# carte_A.net
KiCad netlist of a schematic drawn in EAGLE
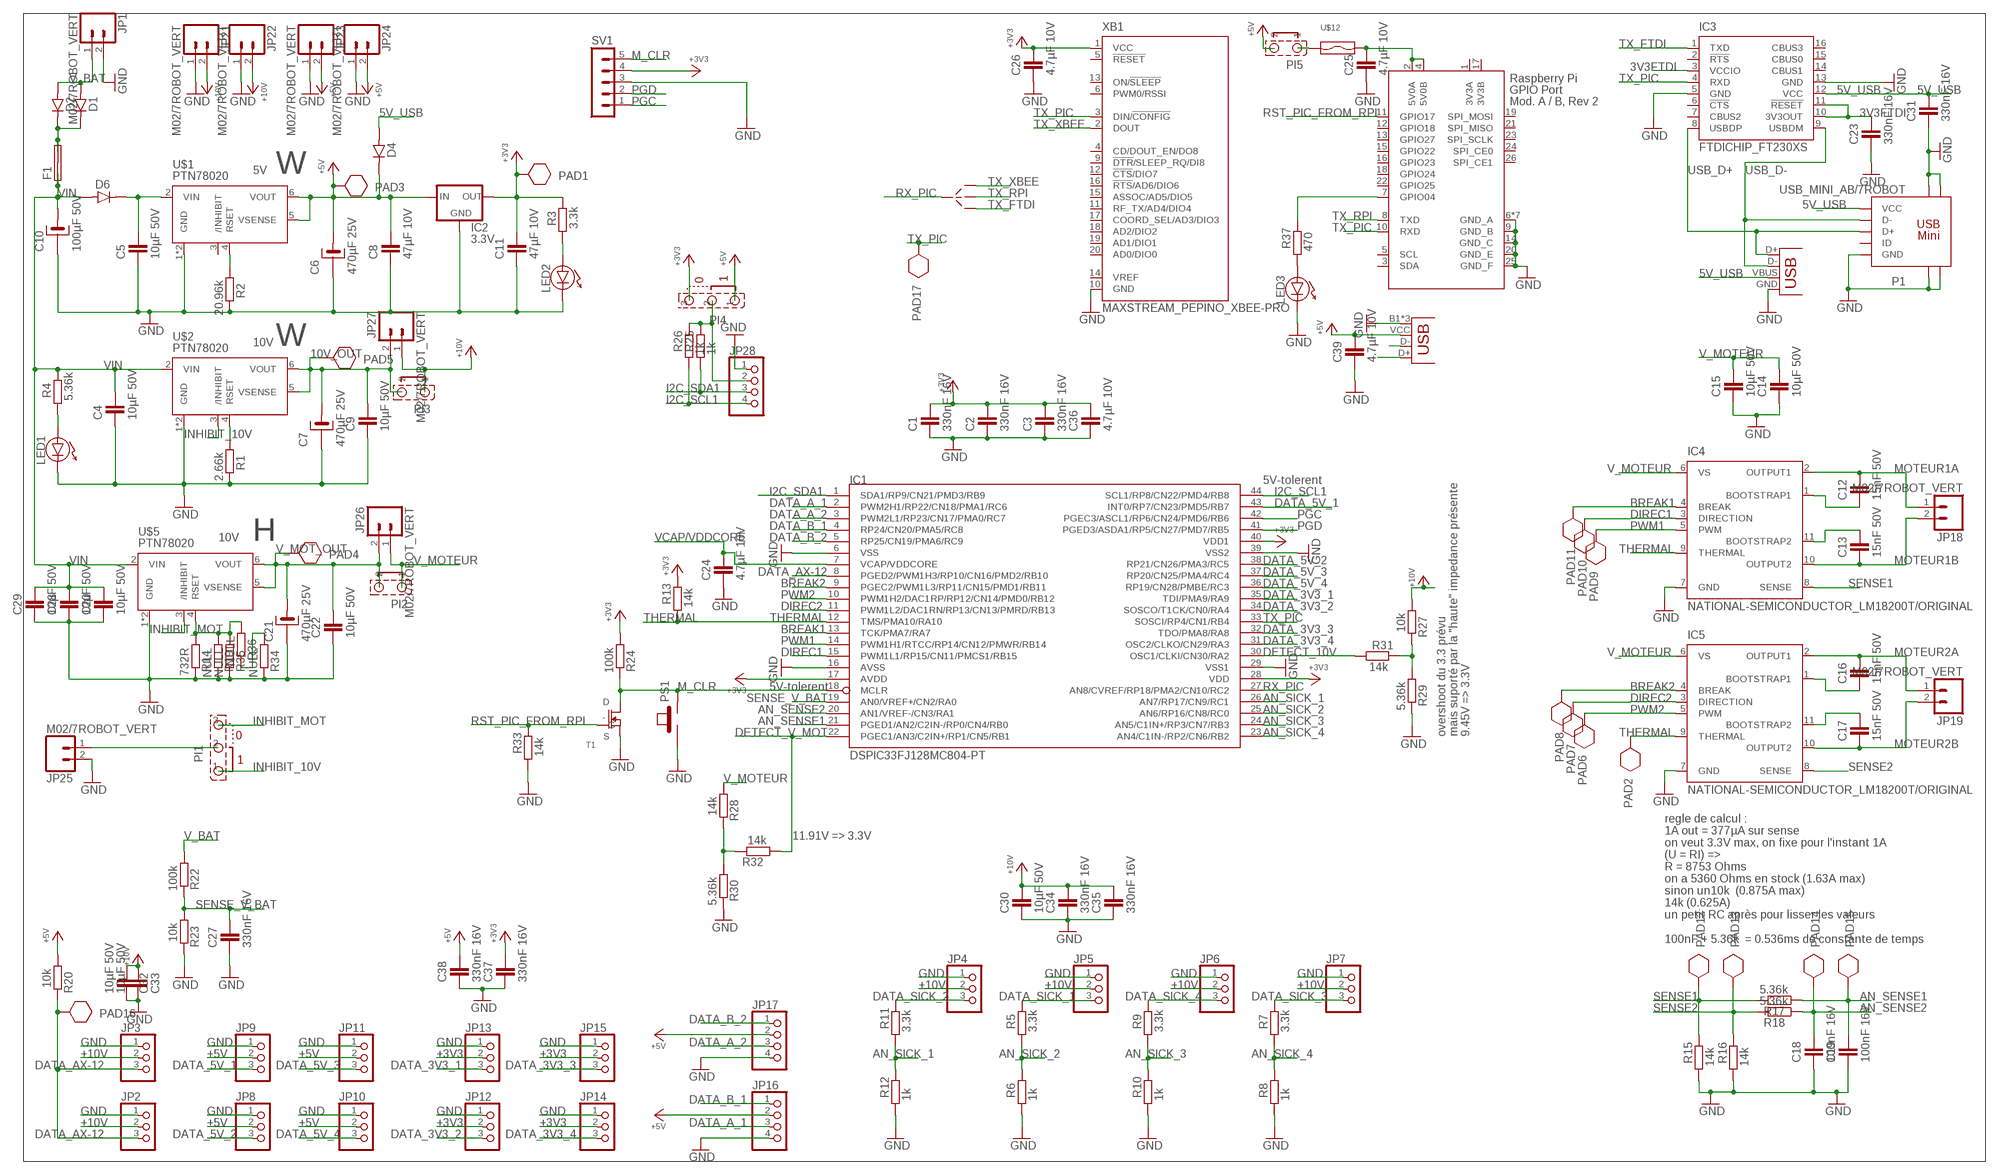
[diagram p0: schematic, sheet 1]

(export (version "E")
  (design (tool "Eeschema 10.0.6"))
  (components
    (comp (ref "C1")
      (value "330nF 16V")
      (footprint "eagle-import:0805")
      (libsource (lib "eagle-import") (part "C_CERAMIQUE/0805"))
    )
    (comp (ref "C2")
      (value "330nF 16V")
      (footprint "eagle-import:0805")
      (libsource (lib "eagle-import") (part "C_CERAMIQUE/0805"))
    )
    (comp (ref "C3")
      (value "330nF 16V")
      (footprint "eagle-import:0805")
      (libsource (lib "eagle-import") (part "C_CERAMIQUE/0805"))
    )
    (comp (ref "C4")
      (value "10µF 50V")
      (footprint "eagle-import:1206")
      (libsource (lib "eagle-import") (part "C_CERAMIQUE/1206"))
    )
    (comp (ref "C5")
      (value "10µF 50V")
      (footprint "eagle-import:1206")
      (libsource (lib "eagle-import") (part "C_CERAMIQUE/1206"))
    )
    (comp (ref "C6")
      (value "470µF 25V")
      (footprint "eagle-import:CHIM8P3.5")
      (libsource (lib "eagle-import") (part "C_CHIMIQUE/RADIAL_8X10_PAS3.5"))
    )
    (comp (ref "C7")
      (value "470µF 25V")
      (footprint "eagle-import:CHIM8P3.5")
      (libsource (lib "eagle-import") (part "C_CHIMIQUE/RADIAL_8X10_PAS3.5"))
    )
    (comp (ref "C8")
      (value "47µF 10V")
      (footprint "eagle-import:1210")
      (libsource (lib "eagle-import") (part "C_CERAMIQUE/1210"))
    )
    (comp (ref "C9")
      (value "10µF 50V")
      (footprint "eagle-import:1206")
      (libsource (lib "eagle-import") (part "C_CERAMIQUE/1206"))
    )
    (comp (ref "C10")
      (value "100µF 50V")
      (footprint "eagle-import:CHIM8P3.5")
      (libsource (lib "eagle-import") (part "C_CHIMIQUE/RADIAL_8X10_PAS3.5"))
    )
    (comp (ref "C11")
      (value "47µF 10V")
      (footprint "eagle-import:1210")
      (libsource (lib "eagle-import") (part "C_CERAMIQUE/1210"))
    )
    (comp (ref "C12")
      (value "15nF 50V")
      (footprint "eagle-import:0805")
      (libsource (lib "eagle-import") (part "C_CERAMIQUE/0805"))
    )
    (comp (ref "C13")
      (value "15nF 50V")
      (footprint "eagle-import:0805")
      (libsource (lib "eagle-import") (part "C_CERAMIQUE/0805"))
    )
    (comp (ref "C14")
      (value "10µF 50V")
      (footprint "eagle-import:1206")
      (libsource (lib "eagle-import") (part "C_CERAMIQUE/1206"))
    )
    (comp (ref "C15")
      (value "10µF 50V")
      (footprint "eagle-import:1206")
      (libsource (lib "eagle-import") (part "C_CERAMIQUE/1206"))
    )
    (comp (ref "C16")
      (value "15nF 50V")
      (footprint "eagle-import:0805")
      (libsource (lib "eagle-import") (part "C_CERAMIQUE/0805"))
    )
    (comp (ref "C17")
      (value "15nF 50V")
      (footprint "eagle-import:0805")
      (libsource (lib "eagle-import") (part "C_CERAMIQUE/0805"))
    )
    (comp (ref "C18")
      (value "100nF 16V")
      (footprint "eagle-import:0805")
      (libsource (lib "eagle-import") (part "C_CERAMIQUE/0805"))
    )
    (comp (ref "C19")
      (value "100nF 16V")
      (footprint "eagle-import:0805")
      (libsource (lib "eagle-import") (part "C_CERAMIQUE/0805"))
    )
    (comp (ref "C20")
      (value "10µF 50V")
      (footprint "eagle-import:1206")
      (libsource (lib "eagle-import") (part "C_CERAMIQUE/1206"))
    )
    (comp (ref "C21")
      (value "470µF 25V")
      (footprint "eagle-import:CHIM8P3.5")
      (libsource (lib "eagle-import") (part "C_CHIMIQUE/RADIAL_8X10_PAS3.5"))
    )
    (comp (ref "C22")
      (value "10µF 50V")
      (footprint "eagle-import:1206")
      (libsource (lib "eagle-import") (part "C_CERAMIQUE/1206"))
    )
    (comp (ref "C23")
      (value "330nF 16V")
      (footprint "eagle-import:0805")
      (libsource (lib "eagle-import") (part "C_CERAMIQUE/0805"))
    )
    (comp (ref "C24")
      (value "4.7µF 10V")
      (footprint "eagle-import:0805")
      (libsource (lib "eagle-import") (part "C_CERAMIQUE/0805"))
    )
    (comp (ref "C25")
      (value "4.7µF 10V")
      (footprint "eagle-import:0805")
      (libsource (lib "eagle-import") (part "C_CERAMIQUE/0805"))
    )
    (comp (ref "C26")
      (value "4.7µF 10V")
      (footprint "eagle-import:0805")
      (libsource (lib "eagle-import") (part "C_CERAMIQUE/0805"))
    )
    (comp (ref "C27")
      (value "330nF 16V")
      (footprint "eagle-import:0805")
      (libsource (lib "eagle-import") (part "C_CERAMIQUE/0805"))
    )
    (comp (ref "C28")
      (value "10µF 50V")
      (footprint "eagle-import:1206")
      (libsource (lib "eagle-import") (part "C_CERAMIQUE/1206"))
    )
    (comp (ref "C29")
      (value "10µF 50V")
      (footprint "eagle-import:1206")
      (libsource (lib "eagle-import") (part "C_CERAMIQUE/1206"))
    )
    (comp (ref "C30")
      (value "10µF 50V")
      (footprint "eagle-import:1206")
      (libsource (lib "eagle-import") (part "C_CERAMIQUE/1206"))
    )
    (comp (ref "C31")
      (value "330nF 16V")
      (footprint "eagle-import:0805")
      (libsource (lib "eagle-import") (part "C_CERAMIQUE/0805"))
    )
    (comp (ref "C32")
      (value "10µF 50V")
      (footprint "eagle-import:1206")
      (libsource (lib "eagle-import") (part "C_CERAMIQUE/1206"))
    )
    (comp (ref "C33")
      (value "10µF 50V")
      (footprint "eagle-import:1206")
      (libsource (lib "eagle-import") (part "C_CERAMIQUE/1206"))
    )
    (comp (ref "C34")
      (value "330nF 16V")
      (footprint "eagle-import:0805")
      (libsource (lib "eagle-import") (part "C_CERAMIQUE/0805"))
    )
    (comp (ref "C35")
      (value "330nF 16V")
      (footprint "eagle-import:0805")
      (libsource (lib "eagle-import") (part "C_CERAMIQUE/0805"))
    )
    (comp (ref "C36")
      (value "4.7µF 10V")
      (footprint "eagle-import:0805")
      (libsource (lib "eagle-import") (part "C_CERAMIQUE/0805"))
    )
    (comp (ref "C37")
      (value "330nF 16V")
      (footprint "eagle-import:0805")
      (libsource (lib "eagle-import") (part "C_CERAMIQUE/0805"))
    )
    (comp (ref "C38")
      (value "330nF 16V")
      (footprint "eagle-import:0805")
      (libsource (lib "eagle-import") (part "C_CERAMIQUE/0805"))
    )
    (comp (ref "C39")
      (value "4.7µF 10V")
      (footprint "eagle-import:0805")
      (libsource (lib "eagle-import") (part "C_CERAMIQUE/0805"))
    )
    (comp (ref "D1")
      (value "DIODES_DIODE/DO41")
      (footprint "eagle-import:DIODES_DO41")
      (libsource (lib "eagle-import") (part "DIODES_DIODE/DO41"))
    )
    (comp (ref "D2")
      (value "DIODES_DIODE/DO41")
      (footprint "eagle-import:DIODES_DO41")
      (libsource (lib "eagle-import") (part "DIODES_DIODE/DO41"))
    )
    (comp (ref "D4")
      (value "DIODES_DIODE/DO41")
      (footprint "eagle-import:DIODES_DO41")
      (libsource (lib "eagle-import") (part "DIODES_DIODE/DO41"))
    )
    (comp (ref "D6")
      (value "DIODES_DIODE/DO41")
      (footprint "eagle-import:DIODES_DO41")
      (libsource (lib "eagle-import") (part "DIODES_DIODE/DO41"))
    )
    (comp (ref "F1")
      (value "PORTE_FUSIBLE")
      (footprint "eagle-import:SHK20L")
      (libsource (lib "eagle-import") (part "PORTE_FUSIBLE"))
    )
    (comp (ref "IC1")
      (value "DSPIC33FJ128MC804-PT")
      (footprint "eagle-import:TQFP44")
      (libsource (lib "eagle-import") (part "DSPIC33FJ128MC804-PT"))
    )
    (comp (ref "IC2")
      (value "3.3V")
      (footprint "eagle-import:V-REG_78XXS")
      (libsource (lib "eagle-import") (part "V-REG_78XXS"))
    )
    (comp (ref "IC3")
      (value "FTDICHIP_FT230XS")
      (footprint "eagle-import:FTDICHIP_SSOP16")
      (libsource (lib "eagle-import") (part "FTDICHIP_FT230XS"))
    )
    (comp (ref "IC4")
      (value "NATIONAL-SEMICONDUCTOR_LM18200T/ORIGINAL")
      (footprint "eagle-import:NATIONAL-SEMICONDUCTOR_TO-220-11")
      (libsource (lib "eagle-import") (part "NATIONAL-SEMICONDUCTOR_LM18200T/ORIGINAL"))
    )
    (comp (ref "IC5")
      (value "NATIONAL-SEMICONDUCTOR_LM18200T/ORIGINAL")
      (footprint "eagle-import:NATIONAL-SEMICONDUCTOR_TO-220-11")
      (libsource (lib "eagle-import") (part "NATIONAL-SEMICONDUCTOR_LM18200T/ORIGINAL"))
    )
    (comp (ref "JP1")
      (value "M02/7ROBOT_VERT")
      (footprint "eagle-import:CONN_5MM")
      (libsource (lib "eagle-import") (part "M02/7ROBOT_VERT"))
    )
    (comp (ref "JP2")
      (value "PINHD-1X3")
      (footprint "eagle-import:1X03")
      (libsource (lib "eagle-import") (part "PINHD-1X3"))
    )
    (comp (ref "JP3")
      (value "PINHD-1X3")
      (footprint "eagle-import:1X03")
      (libsource (lib "eagle-import") (part "PINHD-1X3"))
    )
    (comp (ref "JP4")
      (value "PINHD-1X3")
      (footprint "eagle-import:1X03")
      (libsource (lib "eagle-import") (part "PINHD-1X3"))
    )
    (comp (ref "JP5")
      (value "PINHD-1X3")
      (footprint "eagle-import:1X03")
      (libsource (lib "eagle-import") (part "PINHD-1X3"))
    )
    (comp (ref "JP6")
      (value "PINHD-1X3")
      (footprint "eagle-import:1X03")
      (libsource (lib "eagle-import") (part "PINHD-1X3"))
    )
    (comp (ref "JP7")
      (value "PINHD-1X3")
      (footprint "eagle-import:1X03")
      (libsource (lib "eagle-import") (part "PINHD-1X3"))
    )
    (comp (ref "JP8")
      (value "PINHD-1X3")
      (footprint "eagle-import:1X03")
      (libsource (lib "eagle-import") (part "PINHD-1X3"))
    )
    (comp (ref "JP9")
      (value "PINHD-1X3")
      (footprint "eagle-import:1X03")
      (libsource (lib "eagle-import") (part "PINHD-1X3"))
    )
    (comp (ref "JP10")
      (value "PINHD-1X3")
      (footprint "eagle-import:1X03")
      (libsource (lib "eagle-import") (part "PINHD-1X3"))
    )
    (comp (ref "JP11")
      (value "PINHD-1X3")
      (footprint "eagle-import:1X03")
      (libsource (lib "eagle-import") (part "PINHD-1X3"))
    )
    (comp (ref "JP12")
      (value "PINHD-1X3")
      (footprint "eagle-import:1X03")
      (libsource (lib "eagle-import") (part "PINHD-1X3"))
    )
    (comp (ref "JP13")
      (value "PINHD-1X3")
      (footprint "eagle-import:1X03")
      (libsource (lib "eagle-import") (part "PINHD-1X3"))
    )
    (comp (ref "JP14")
      (value "PINHD-1X3")
      (footprint "eagle-import:1X03")
      (libsource (lib "eagle-import") (part "PINHD-1X3"))
    )
    (comp (ref "JP15")
      (value "PINHD-1X3")
      (footprint "eagle-import:1X03")
      (libsource (lib "eagle-import") (part "PINHD-1X3"))
    )
    (comp (ref "JP16")
      (value "PINHD-1X4")
      (footprint "eagle-import:1X04")
      (libsource (lib "eagle-import") (part "PINHD-1X4"))
    )
    (comp (ref "JP17")
      (value "PINHD-1X4")
      (footprint "eagle-import:1X04")
      (libsource (lib "eagle-import") (part "PINHD-1X4"))
    )
    (comp (ref "JP18")
      (value "M02/7ROBOT_VERT")
      (footprint "eagle-import:CONN_5MM")
      (libsource (lib "eagle-import") (part "M02/7ROBOT_VERT"))
    )
    (comp (ref "JP19")
      (value "M02/7ROBOT_VERT")
      (footprint "eagle-import:CONN_5MM")
      (libsource (lib "eagle-import") (part "M02/7ROBOT_VERT"))
    )
    (comp (ref "JP20")
      (value "USB-B")
      (footprint "eagle-import:SPARKFUN-CONNECTORS_USB-B-PTH")
      (libsource (lib "eagle-import") (part "SPARKFUN-CONNECTORS_USBPTH"))
    )
    (comp (ref "JP21")
      (value "M02/7ROBOT_VERT")
      (footprint "eagle-import:CONN_5MM")
      (libsource (lib "eagle-import") (part "M02/7ROBOT_VERT"))
    )
    (comp (ref "JP22")
      (value "M02/7ROBOT_VERT")
      (footprint "eagle-import:CONN_5MM")
      (libsource (lib "eagle-import") (part "M02/7ROBOT_VERT"))
    )
    (comp (ref "JP23")
      (value "M02/7ROBOT_VERT")
      (footprint "eagle-import:CONN_5MM")
      (libsource (lib "eagle-import") (part "M02/7ROBOT_VERT"))
    )
    (comp (ref "JP24")
      (value "M02/7ROBOT_VERT")
      (footprint "eagle-import:CONN_5MM")
      (libsource (lib "eagle-import") (part "M02/7ROBOT_VERT"))
    )
    (comp (ref "JP25")
      (value "M02/7ROBOT_VERT")
      (footprint "eagle-import:CONN_5MM")
      (libsource (lib "eagle-import") (part "M02/7ROBOT_VERT"))
    )
    (comp (ref "JP26")
      (value "M02/7ROBOT_VERT")
      (footprint "eagle-import:CONN_5MM")
      (libsource (lib "eagle-import") (part "M02/7ROBOT_VERT"))
    )
    (comp (ref "JP27")
      (value "M02/7ROBOT_VERT")
      (footprint "eagle-import:CONN_5MM")
      (libsource (lib "eagle-import") (part "M02/7ROBOT_VERT"))
    )
    (comp (ref "JP28")
      (value "PINHD-1X4")
      (footprint "eagle-import:1X04")
      (libsource (lib "eagle-import") (part "PINHD-1X4"))
    )
    (comp (ref "JP29")
      (value "USB/VERT")
      (footprint "eagle-import:USB-A-FEMALE_VERTICAL")
      (libsource (lib "eagle-import") (part "USB/VERT"))
    )
    (comp (ref "LED1")
      (value "OPTO_OSC_LED/5MM")
      (footprint "eagle-import:OPTO_OSC_LED5")
      (libsource (lib "eagle-import") (part "OPTO_OSC_LED/5MM"))
    )
    (comp (ref "LED2")
      (value "OPTO_OSC_LED/5MM")
      (footprint "eagle-import:OPTO_OSC_LED5")
      (libsource (lib "eagle-import") (part "OPTO_OSC_LED/5MM"))
    )
    (comp (ref "LED3")
      (value "LED/1206")
      (footprint "eagle-import:LED1206")
      (libsource (lib "eagle-import") (part "LED/1206"))
    )
    (comp (ref "P1")
      (value "USB_MINI_AB/7ROBOT")
      (footprint "eagle-import:USB_MINI_AB_7ROBOT")
      (libsource (lib "eagle-import") (part "USB_MINI_AB/7ROBOT"))
    )
    (comp (ref "PAD1")
      (value "STRAP_PAD/CMS2")
      (footprint "eagle-import:STRAP_PAD_CMS_2")
      (libsource (lib "eagle-import") (part "STRAP_PAD/CMS2"))
    )
    (comp (ref "PAD2")
      (value "STRAP_PAD/CMS1_5")
      (footprint "eagle-import:STRAP_PAD_CMS_1_5")
      (libsource (lib "eagle-import") (part "STRAP_PAD/CMS1_5"))
    )
    (comp (ref "PAD3")
      (value "STRAP_PAD/CMS2")
      (footprint "eagle-import:STRAP_PAD_CMS_2")
      (libsource (lib "eagle-import") (part "STRAP_PAD/CMS2"))
    )
    (comp (ref "PAD4")
      (value "STRAP_PAD/CMS2")
      (footprint "eagle-import:STRAP_PAD_CMS_2")
      (libsource (lib "eagle-import") (part "STRAP_PAD/CMS2"))
    )
    (comp (ref "PAD5")
      (value "STRAP_PAD/CMS2")
      (footprint "eagle-import:STRAP_PAD_CMS_2")
      (libsource (lib "eagle-import") (part "STRAP_PAD/CMS2"))
    )
    (comp (ref "PAD6")
      (value "STRAP_PAD/CMS1_5")
      (footprint "eagle-import:STRAP_PAD_CMS_1_5")
      (libsource (lib "eagle-import") (part "STRAP_PAD/CMS1_5"))
    )
    (comp (ref "PAD7")
      (value "STRAP_PAD/CMS1_5")
      (footprint "eagle-import:STRAP_PAD_CMS_1_5")
      (libsource (lib "eagle-import") (part "STRAP_PAD/CMS1_5"))
    )
    (comp (ref "PAD8")
      (value "STRAP_PAD/CMS1_5")
      (footprint "eagle-import:STRAP_PAD_CMS_1_5")
      (libsource (lib "eagle-import") (part "STRAP_PAD/CMS1_5"))
    )
    (comp (ref "PAD9")
      (value "STRAP_PAD/CMS1_5")
      (footprint "eagle-import:STRAP_PAD_CMS_1_5")
      (libsource (lib "eagle-import") (part "STRAP_PAD/CMS1_5"))
    )
    (comp (ref "PAD10")
      (value "STRAP_PAD/CMS1_5")
      (footprint "eagle-import:STRAP_PAD_CMS_1_5")
      (libsource (lib "eagle-import") (part "STRAP_PAD/CMS1_5"))
    )
    (comp (ref "PAD11")
      (value "STRAP_PAD/CMS1_5")
      (footprint "eagle-import:STRAP_PAD_CMS_1_5")
      (libsource (lib "eagle-import") (part "STRAP_PAD/CMS1_5"))
    )
    (comp (ref "PAD12")
      (value "STRAP_PAD/CMS1_5")
      (footprint "eagle-import:STRAP_PAD_CMS_1_5")
      (libsource (lib "eagle-import") (part "STRAP_PAD/CMS1_5"))
    )
    (comp (ref "PAD13")
      (value "STRAP_PAD/CMS1_5")
      (footprint "eagle-import:STRAP_PAD_CMS_1_5")
      (libsource (lib "eagle-import") (part "STRAP_PAD/CMS1_5"))
    )
    (comp (ref "PAD14")
      (value "STRAP_PAD/CMS1_5")
      (footprint "eagle-import:STRAP_PAD_CMS_1_5")
      (libsource (lib "eagle-import") (part "STRAP_PAD/CMS1_5"))
    )
    (comp (ref "PAD15")
      (value "STRAP_PAD/CMS1_5")
      (footprint "eagle-import:STRAP_PAD_CMS_1_5")
      (libsource (lib "eagle-import") (part "STRAP_PAD/CMS1_5"))
    )
    (comp (ref "PAD16")
      (value "STRAP_PAD/CMS1_5")
      (footprint "eagle-import:STRAP_PAD_CMS_1_5")
      (libsource (lib "eagle-import") (part "STRAP_PAD/CMS1_5"))
    )
    (comp (ref "PAD17")
      (value "STRAP_PAD/CMS2")
      (footprint "eagle-import:STRAP_PAD_CMS_2")
      (libsource (lib "eagle-import") (part "STRAP_PAD/CMS2"))
    )
    (comp (ref "PI1")
      (value "STCMS_3/CMS")
      (footprint "eagle-import:STCMS_3")
      (libsource (lib "eagle-import") (part "STCMS_3/CMS"))
    )
    (comp (ref "PI2")
      (value "STCMS_2")
      (footprint "eagle-import:STCMS_2")
      (libsource (lib "eagle-import") (part "STCMS_2"))
    )
    (comp (ref "PI3")
      (value "STCMS_2")
      (footprint "eagle-import:STCMS_2")
      (libsource (lib "eagle-import") (part "STCMS_2"))
    )
    (comp (ref "PI4")
      (value "STCMS_3/CMS")
      (footprint "eagle-import:STCMS_3")
      (libsource (lib "eagle-import") (part "STCMS_3/CMS"))
    )
    (comp (ref "PI5")
      (value "STCMS_2")
      (footprint "eagle-import:STCMS_2")
      (libsource (lib "eagle-import") (part "STCMS_2"))
    )
    (comp (ref "PS1")
      (value "ELECTROMECA_PEPINO_POUSSOIR/D_MINI")
      (footprint "eagle-import:ELECTROMECA_PEPINO_B3F")
      (libsource (lib "eagle-import") (part "ELECTROMECA_PEPINO_POUSSOIR/D_MINI"))
    )
    (comp (ref "R1")
      (value "2.66k")
      (footprint "eagle-import:0805")
      (libsource (lib "eagle-import") (part "RES/0805"))
    )
    (comp (ref "R2")
      (value "20.96k")
      (footprint "eagle-import:0805")
      (libsource (lib "eagle-import") (part "RES/0805"))
    )
    (comp (ref "R3")
      (value "3.3k")
      (footprint "eagle-import:0805")
      (libsource (lib "eagle-import") (part "RES/0805"))
    )
    (comp (ref "R4")
      (value "5.36k")
      (footprint "eagle-import:0805")
      (libsource (lib "eagle-import") (part "RES/0805"))
    )
    (comp (ref "R5")
      (value "3.3k")
      (footprint "eagle-import:0805")
      (libsource (lib "eagle-import") (part "RES/0805"))
    )
    (comp (ref "R6")
      (value "1k")
      (footprint "eagle-import:0805")
      (libsource (lib "eagle-import") (part "RES/0805"))
    )
    (comp (ref "R7")
      (value "3.3k")
      (footprint "eagle-import:0805")
      (libsource (lib "eagle-import") (part "RES/0805"))
    )
    (comp (ref "R8")
      (value "1k")
      (footprint "eagle-import:0805")
      (libsource (lib "eagle-import") (part "RES/0805"))
    )
    (comp (ref "R9")
      (value "3.3k")
      (footprint "eagle-import:0805")
      (libsource (lib "eagle-import") (part "RES/0805"))
    )
    (comp (ref "R10")
      (value "1k")
      (footprint "eagle-import:0805")
      (libsource (lib "eagle-import") (part "RES/0805"))
    )
    (comp (ref "R11")
      (value "3.3k")
      (footprint "eagle-import:0805")
      (libsource (lib "eagle-import") (part "RES/0805"))
    )
    (comp (ref "R12")
      (value "1k")
      (footprint "eagle-import:0805")
      (libsource (lib "eagle-import") (part "RES/0805"))
    )
    (comp (ref "R13")
      (value "14k")
      (footprint "eagle-import:0805")
      (libsource (lib "eagle-import") (part "RES/0805"))
    )
    (comp (ref "R14")
      (value "732R")
      (footprint "eagle-import:0805")
      (libsource (lib "eagle-import") (part "RES/0805"))
    )
    (comp (ref "R15")
      (value "14k")
      (footprint "eagle-import:0805")
      (libsource (lib "eagle-import") (part "RES/0805"))
    )
    (comp (ref "R16")
      (value "14k")
      (footprint "eagle-import:0805")
      (libsource (lib "eagle-import") (part "RES/0805"))
    )
    (comp (ref "R17")
      (value "5.36k")
      (footprint "eagle-import:0805")
      (libsource (lib "eagle-import") (part "RES/0805"))
    )
    (comp (ref "R18")
      (value "5.36k")
      (footprint "eagle-import:0805")
      (libsource (lib "eagle-import") (part "RES/0805"))
    )
    (comp (ref "R19")
      (value "NULL")
      (footprint "eagle-import:0805")
      (libsource (lib "eagle-import") (part "RES/0805"))
    )
    (comp (ref "R20")
      (value "10k")
      (footprint "eagle-import:1206")
      (libsource (lib "eagle-import") (part "RES/1206"))
    )
    (comp (ref "R22")
      (value "100k")
      (footprint "eagle-import:1206")
      (libsource (lib "eagle-import") (part "RES/1206"))
    )
    (comp (ref "R23")
      (value "10k")
      (footprint "eagle-import:1206")
      (libsource (lib "eagle-import") (part "RES/1206"))
    )
    (comp (ref "R24")
      (value "100k")
      (footprint "eagle-import:1206")
      (libsource (lib "eagle-import") (part "RES/1206"))
    )
    (comp (ref "R25")
      (value "1k")
      (footprint "eagle-import:0805")
      (libsource (lib "eagle-import") (part "RES/0805"))
    )
    (comp (ref "R26")
      (value "1k")
      (footprint "eagle-import:0805")
      (libsource (lib "eagle-import") (part "RES/0805"))
    )
    (comp (ref "R27")
      (value "10k")
      (footprint "eagle-import:1206")
      (libsource (lib "eagle-import") (part "RES/1206"))
    )
    (comp (ref "R28")
      (value "14k")
      (footprint "eagle-import:0805")
      (libsource (lib "eagle-import") (part "RES/0805"))
    )
    (comp (ref "R29")
      (value "5.36k")
      (footprint "eagle-import:0805")
      (libsource (lib "eagle-import") (part "RES/0805"))
    )
    (comp (ref "R30")
      (value "5.36k")
      (footprint "eagle-import:0805")
      (libsource (lib "eagle-import") (part "RES/0805"))
    )
    (comp (ref "R31")
      (value "14k")
      (footprint "eagle-import:0805")
      (libsource (lib "eagle-import") (part "RES/0805"))
    )
    (comp (ref "R32")
      (value "14k")
      (footprint "eagle-import:0805")
      (libsource (lib "eagle-import") (part "RES/0805"))
    )
    (comp (ref "R33")
      (value "14k")
      (footprint "eagle-import:0805")
      (libsource (lib "eagle-import") (part "RES/0805"))
    )
    (comp (ref "R34")
      (value "NULL")
      (footprint "eagle-import:0805")
      (libsource (lib "eagle-import") (part "RES/0805"))
    )
    (comp (ref "R35")
      (value "NULL")
      (footprint "eagle-import:0805")
      (libsource (lib "eagle-import") (part "RES/0805"))
    )
    (comp (ref "R36")
      (value "NULL")
      (footprint "eagle-import:0805")
      (libsource (lib "eagle-import") (part "RES/0805"))
    )
    (comp (ref "R37")
      (value "470")
      (footprint "eagle-import:0805")
      (libsource (lib "eagle-import") (part "RES/0805"))
    )
    (comp (ref "SV1")
      (value "CON-LSTB_MA05-1")
      (footprint "eagle-import:CON-LSTB_MA05-1")
      (libsource (lib "eagle-import") (part "CON-LSTB_MA05-1"))
    )
    (comp (ref "T1")
      (value "MOS_N/SOT23")
      (footprint "eagle-import:SOT23")
      (libsource (lib "eagle-import") (part "MOS_N/SOT23"))
    )
    (comp (ref "U$1")
      (value "PTN78020")
      (footprint "eagle-import:PTN78020")
      (libsource (lib "eagle-import") (part "PTN78020"))
    )
    (comp (ref "U$2")
      (value "PTN78020")
      (footprint "eagle-import:PTN78020")
      (libsource (lib "eagle-import") (part "PTN78020"))
    )
    (comp (ref "U$5")
      (value "PTN78020")
      (footprint "eagle-import:PTN78020")
      (libsource (lib "eagle-import") (part "PTN78020"))
    )
    (comp (ref "U$9")
      (value "STCMS_4")
      (footprint "eagle-import:STCMS_4")
      (libsource (lib "eagle-import") (part "STCMS_4"))
    )
    (comp (ref "U$12")
      (value "FUSE_REARMABLE/1206")
      (footprint "eagle-import:1206")
      (libsource (lib "eagle-import") (part "FUSE_REARMABLE/1206"))
    )
    (comp (ref "X1")
      (value "RASPI_BOARD_B-#_E6P")
      (footprint "eagle-import:RASPI_BOARD_AB-_EDGES_6DRILL_PAD")
      (libsource (lib "eagle-import") (part "RASPI_BOARD_B-#_E6P"))
    )
    (comp (ref "XB1")
      (value "MAXSTREAM_PEPINO_XBEE-PRO")
      (footprint "eagle-import:MAXSTREAM_PEPINO_XBEE-PRO")
      (fields (field (name "MPN") "XBP24-AWI-001"))
      (libsource (lib "eagle-import") (part "MAXSTREAM_PEPINO_XBEE-PRO"))
    )
  )
  (nets
    (net (code "1") (name "+3V3") (class "Default")
      (node (ref "C1") (pin "1") (pinfunction "1_1") (pintype "passive"))
      (node (ref "C11") (pin "1") (pinfunction "1_1") (pintype "passive"))
      (node (ref "C2") (pin "1") (pinfunction "1_1") (pintype "passive"))
      (node (ref "C26") (pin "1") (pinfunction "1_1") (pintype "passive"))
      (node (ref "C3") (pin "1") (pinfunction "1_1") (pintype "passive"))
      (node (ref "C36") (pin "1") (pinfunction "1_1") (pintype "passive"))
      (node (ref "C37") (pin "1") (pinfunction "1_1") (pintype "passive"))
      (node (ref "IC1") (pin "17") (pinfunction "AVDD_17") (pintype "power_in"))
      (node (ref "IC1") (pin "28") (pinfunction "VDD_28") (pintype "power_in"))
      (node (ref "IC1") (pin "40") (pinfunction "VDD1_40") (pintype "power_in"))
      (node (ref "IC2") (pin "OUT") (pinfunction "OUT_OUT") (pintype "passive"))
      (node (ref "JP12") (pin "2") (pinfunction "2_2") (pintype "passive"))
      (node (ref "JP13") (pin "2") (pinfunction "2_2") (pintype "passive"))
      (node (ref "JP14") (pin "2") (pinfunction "2_2") (pintype "passive"))
      (node (ref "JP15") (pin "2") (pinfunction "2_2") (pintype "passive"))
      (node (ref "PAD1") (pin "P$1") (pinfunction "P$1_P$1") (pintype "bidirectional"))
      (node (ref "PI4") (pin "3") (pinfunction "3_3") (pintype "bidirectional"))
      (node (ref "R13") (pin "2") (pinfunction "2_2") (pintype "passive"))
      (node (ref "R24") (pin "1") (pinfunction "1_1") (pintype "passive"))
      (node (ref "R3") (pin "2") (pinfunction "2_2") (pintype "passive"))
      (node (ref "SV1") (pin "4") (pinfunction "4_4") (pintype "passive"))
      (node (ref "XB1") (pin "1") (pinfunction "VCC_1") (pintype "power_in"))
    )
    (net (code "2") (name "+5V") (class "Default")
      (node (ref "C38") (pin "1") (pinfunction "1_1") (pintype "passive"))
      (node (ref "C39") (pin "1") (pinfunction "1_1") (pintype "passive"))
      (node (ref "C6") (pin "P") (pinfunction "P_P") (pintype "passive"))
      (node (ref "C8") (pin "1") (pinfunction "1_1") (pintype "passive"))
      (node (ref "D4") (pin "K") (pinfunction "K_K") (pintype "passive"))
      (node (ref "IC2") (pin "IN") (pinfunction "IN_IN") (pintype "input"))
      (node (ref "JP10") (pin "2") (pinfunction "2_2") (pintype "passive"))
      (node (ref "JP11") (pin "2") (pinfunction "2_2") (pintype "passive"))
      (node (ref "JP16") (pin "2") (pinfunction "2_2") (pintype "passive"))
      (node (ref "JP17") (pin "2") (pinfunction "2_2") (pintype "passive"))
      (node (ref "JP23") (pin "2") (pinfunction "2_2") (pintype "passive"))
      (node (ref "JP24") (pin "2") (pinfunction "2_2") (pintype "passive"))
      (node (ref "JP29") (pin "VCC") (pinfunction "VBUS_VCC") (pintype "bidirectional"))
      (node (ref "JP8") (pin "2") (pinfunction "2_2") (pintype "passive"))
      (node (ref "JP9") (pin "2") (pinfunction "2_2") (pintype "passive"))
      (node (ref "PAD3") (pin "P$1") (pinfunction "P$1_P$1") (pintype "bidirectional"))
      (node (ref "PI4") (pin "1") (pinfunction "1_1") (pintype "bidirectional"))
      (node (ref "PI5") (pin "2") (pinfunction "2_2") (pintype "bidirectional"))
      (node (ref "R20") (pin "1") (pinfunction "1_1") (pintype "passive"))
      (node (ref "U$1") (pin "5") (pinfunction "VSENSE_5") (pintype "bidirectional"))
      (node (ref "U$1") (pin "6") (pinfunction "VOUT_6") (pintype "bidirectional"))
    )
    (net (code "3") (name "+10V") (class "Default")
      (node (ref "C30") (pin "1") (pinfunction "1_1") (pintype "passive"))
      (node (ref "C32") (pin "1") (pinfunction "1_1") (pintype "passive"))
      (node (ref "C33") (pin "1") (pinfunction "1_1") (pintype "passive"))
      (node (ref "C34") (pin "1") (pinfunction "1_1") (pintype "passive"))
      (node (ref "C35") (pin "1") (pinfunction "1_1") (pintype "passive"))
      (node (ref "JP2") (pin "2") (pinfunction "2_2") (pintype "passive"))
      (node (ref "JP21") (pin "2") (pinfunction "2_2") (pintype "passive"))
      (node (ref "JP22") (pin "2") (pinfunction "2_2") (pintype "passive"))
      (node (ref "JP27") (pin "1") (pinfunction "1_1") (pintype "passive"))
      (node (ref "JP3") (pin "2") (pinfunction "2_2") (pintype "passive"))
      (node (ref "JP4") (pin "2") (pinfunction "2_2") (pintype "passive"))
      (node (ref "JP5") (pin "2") (pinfunction "2_2") (pintype "passive"))
      (node (ref "JP6") (pin "2") (pinfunction "2_2") (pintype "passive"))
      (node (ref "JP7") (pin "2") (pinfunction "2_2") (pintype "passive"))
      (node (ref "PI3") (pin "1") (pinfunction "1_1") (pintype "bidirectional"))
      (node (ref "R27") (pin "1") (pinfunction "1_1") (pintype "passive"))
    )
    (net (code "4") (name "/3V3A") (class "Default")
      (node (ref "X1") (pin "1") (pinfunction "3V3A_1") (pintype "power_in"))
    )
    (net (code "5") (name "/3V3B") (class "Default")
      (node (ref "X1") (pin "17") (pinfunction "3V3B_17") (pintype "power_in"))
    )
    (net (code "6") (name "/3V3FTDI") (class "Default")
      (node (ref "C23") (pin "1") (pinfunction "1_1") (pintype "passive"))
      (node (ref "IC3") (pin "10") (pinfunction "3V3OUT_10") (pintype "output"))
      (node (ref "IC3") (pin "11") (pinfunction "~{RESET}_11") (pintype "input"))
      (node (ref "IC3") (pin "3") (pinfunction "VCCIO_3") (pintype "power_in"))
    )
    (net (code "7") (name "/5V_USB") (class "Default")
      (node (ref "C31") (pin "1") (pinfunction "1_1") (pintype "passive"))
      (node (ref "D4") (pin "A") (pinfunction "A_A") (pintype "passive"))
      (node (ref "IC3") (pin "12") (pinfunction "VCC_12") (pintype "power_in"))
      (node (ref "JP20") (pin "VBUS") (pinfunction "VBUS_VBUS") (pintype "bidirectional"))
      (node (ref "P1") (pin "1") (pinfunction "VCC_1") (pintype "bidirectional"))
    )
    (net (code "8") (name "/10V_OUT") (class "Default")
      (node (ref "C7") (pin "P") (pinfunction "P_P") (pintype "passive"))
      (node (ref "C9") (pin "1") (pinfunction "1_1") (pintype "passive"))
      (node (ref "JP27") (pin "2") (pinfunction "2_2") (pintype "passive"))
      (node (ref "PAD5") (pin "P$1") (pinfunction "P$1_P$1") (pintype "bidirectional"))
      (node (ref "PI3") (pin "2") (pinfunction "2_2") (pintype "bidirectional"))
      (node (ref "U$2") (pin "5") (pinfunction "VSENSE_5") (pintype "bidirectional"))
      (node (ref "U$2") (pin "6") (pinfunction "VOUT_6") (pintype "bidirectional"))
    )
    (net (code "9") (name "/AN_SENSE1") (class "Default")
      (node (ref "C19") (pin "1") (pinfunction "1_1") (pintype "passive"))
      (node (ref "IC1") (pin "21") (pinfunction "PGED1/AN2/C2IN-/RP0/CN4/RB0_21") (pintype "bidirectional"))
      (node (ref "PAD15") (pin "P$1") (pinfunction "P$1_P$1") (pintype "bidirectional"))
      (node (ref "R17") (pin "1") (pinfunction "1_1") (pintype "passive"))
    )
    (net (code "10") (name "/AN_SENSE2") (class "Default")
      (node (ref "C18") (pin "1") (pinfunction "1_1") (pintype "passive"))
      (node (ref "IC1") (pin "20") (pinfunction "AN1/VREF-/CN3/RA1_20") (pintype "bidirectional"))
      (node (ref "PAD14") (pin "P$1") (pinfunction "P$1_P$1") (pintype "bidirectional"))
      (node (ref "R18") (pin "1") (pinfunction "1_1") (pintype "passive"))
    )
    (net (code "11") (name "/AN_SICK_1") (class "Default")
      (node (ref "IC1") (pin "26") (pinfunction "AN7/RP17/CN9/RC1_26") (pintype "bidirectional"))
      (node (ref "R11") (pin "1") (pinfunction "1_1") (pintype "passive"))
      (node (ref "R12") (pin "2") (pinfunction "2_2") (pintype "passive"))
    )
    (net (code "12") (name "/AN_SICK_2") (class "Default")
      (node (ref "IC1") (pin "25") (pinfunction "AN6/RP16/CN8/RC0_25") (pintype "bidirectional"))
      (node (ref "R5") (pin "1") (pinfunction "1_1") (pintype "passive"))
      (node (ref "R6") (pin "2") (pinfunction "2_2") (pintype "passive"))
    )
    (net (code "13") (name "/AN_SICK_3") (class "Default")
      (node (ref "IC1") (pin "24") (pinfunction "AN5/C1IN+/RP3/CN7/RB3_24") (pintype "bidirectional"))
      (node (ref "R10") (pin "2") (pinfunction "2_2") (pintype "passive"))
      (node (ref "R9") (pin "1") (pinfunction "1_1") (pintype "passive"))
    )
    (net (code "14") (name "/AN_SICK_4") (class "Default")
      (node (ref "IC1") (pin "23") (pinfunction "AN4/C1IN-/RP2/CN6/RB2_23") (pintype "bidirectional"))
      (node (ref "R7") (pin "1") (pinfunction "1_1") (pintype "passive"))
      (node (ref "R8") (pin "2") (pinfunction "2_2") (pintype "passive"))
    )
    (net (code "15") (name "/BREAK1") (class "Default")
      (node (ref "IC1") (pin "13") (pinfunction "TCK/PMA7/RA7_13") (pintype "bidirectional"))
      (node (ref "IC4") (pin "4") (pinfunction "BREAK_4") (pintype "input"))
      (node (ref "PAD11") (pin "P$1") (pinfunction "P$1_P$1") (pintype "bidirectional"))
    )
    (net (code "16") (name "/BREAK2") (class "Default")
      (node (ref "IC1") (pin "9") (pinfunction "PGEC2/PWM1L3/RP11/CN15/PMD1/RB11_9") (pintype "bidirectional"))
      (node (ref "IC5") (pin "4") (pinfunction "BREAK_4") (pintype "input"))
      (node (ref "PAD8") (pin "P$1") (pinfunction "P$1_P$1") (pintype "bidirectional"))
    )
    (net (code "17") (name "/DATA_3V3_1") (class "Default")
      (node (ref "IC1") (pin "35") (pinfunction "TDI/PMA9/RA9_35") (pintype "bidirectional"))
      (node (ref "JP13") (pin "3") (pinfunction "3_3") (pintype "passive"))
    )
    (net (code "18") (name "/DATA_3V3_2") (class "Default")
      (node (ref "IC1") (pin "34") (pinfunction "SOSCO/T1CK/CN0/RA4_34") (pintype "bidirectional"))
      (node (ref "JP12") (pin "3") (pinfunction "3_3") (pintype "passive"))
    )
    (net (code "19") (name "/DATA_3V3_3") (class "Default")
      (node (ref "IC1") (pin "32") (pinfunction "TDO/PMA8/RA8_32") (pintype "bidirectional"))
      (node (ref "JP15") (pin "3") (pinfunction "3_3") (pintype "passive"))
    )
    (net (code "20") (name "/DATA_3V3_4") (class "Default")
      (node (ref "IC1") (pin "31") (pinfunction "OSC2/CLKO/CN29/RA3_31") (pintype "bidirectional"))
      (node (ref "JP14") (pin "3") (pinfunction "3_3") (pintype "passive"))
    )
    (net (code "21") (name "/DATA_5V_1") (class "Default")
      (node (ref "IC1") (pin "43") (pinfunction "INT0/RP7/CN23/PMD5/RB7_43") (pintype "bidirectional"))
      (node (ref "JP9") (pin "3") (pinfunction "3_3") (pintype "passive"))
    )
    (net (code "22") (name "/DATA_5V_2") (class "Default")
      (node (ref "IC1") (pin "38") (pinfunction "RP21/CN26/PMA3/RC5_38") (pintype "bidirectional"))
      (node (ref "JP8") (pin "3") (pinfunction "3_3") (pintype "passive"))
    )
    (net (code "23") (name "/DATA_5V_3") (class "Default")
      (node (ref "IC1") (pin "37") (pinfunction "RP20/CN25/PMA4/RC4_37") (pintype "bidirectional"))
      (node (ref "JP11") (pin "3") (pinfunction "3_3") (pintype "passive"))
    )
    (net (code "24") (name "/DATA_5V_4") (class "Default")
      (node (ref "IC1") (pin "36") (pinfunction "RP19/CN28/PMBE/RC3_36") (pintype "bidirectional"))
      (node (ref "JP10") (pin "3") (pinfunction "3_3") (pintype "passive"))
    )
    (net (code "25") (name "/DATA_AX-12") (class "Default")
      (node (ref "IC1") (pin "8") (pinfunction "PGED2/PWM1H3/RP10/CN16/PMD2/RB10_8") (pintype "bidirectional"))
      (node (ref "JP2") (pin "3") (pinfunction "3_3") (pintype "passive"))
      (node (ref "JP3") (pin "3") (pinfunction "3_3") (pintype "passive"))
      (node (ref "PAD16") (pin "P$1") (pinfunction "P$1_P$1") (pintype "bidirectional"))
      (node (ref "R20") (pin "2") (pinfunction "2_2") (pintype "passive"))
    )
    (net (code "26") (name "/DATA_A_1") (class "Default")
      (node (ref "IC1") (pin "2") (pinfunction "PWM2H1/RP22/CN18/PMA1/RC6_2") (pintype "bidirectional"))
      (node (ref "JP16") (pin "3") (pinfunction "3_3") (pintype "passive"))
    )
    (net (code "27") (name "/DATA_A_2") (class "Default")
      (node (ref "IC1") (pin "3") (pinfunction "PWM2L1/RP23/CN17/PMA0/RC7_3") (pintype "bidirectional"))
      (node (ref "JP17") (pin "3") (pinfunction "3_3") (pintype "passive"))
    )
    (net (code "28") (name "/DATA_B_1") (class "Default")
      (node (ref "IC1") (pin "4") (pinfunction "RP24/CN20/PMA5/RC8_4") (pintype "bidirectional"))
      (node (ref "JP16") (pin "1") (pinfunction "1_1") (pintype "passive"))
    )
    (net (code "29") (name "/DATA_B_2") (class "Default")
      (node (ref "IC1") (pin "5") (pinfunction "RP25/CN19/PMA6/RC9_5") (pintype "bidirectional"))
      (node (ref "JP17") (pin "1") (pinfunction "1_1") (pintype "passive"))
    )
    (net (code "30") (name "/DATA_SICK_1") (class "Default")
      (node (ref "JP5") (pin "3") (pinfunction "3_3") (pintype "passive"))
      (node (ref "R5") (pin "2") (pinfunction "2_2") (pintype "passive"))
    )
    (net (code "31") (name "/DATA_SICK_2") (class "Default")
      (node (ref "JP4") (pin "3") (pinfunction "3_3") (pintype "passive"))
      (node (ref "R11") (pin "2") (pinfunction "2_2") (pintype "passive"))
    )
    (net (code "32") (name "/DATA_SICK_3") (class "Default")
      (node (ref "JP7") (pin "3") (pinfunction "3_3") (pintype "passive"))
      (node (ref "R7") (pin "2") (pinfunction "2_2") (pintype "passive"))
    )
    (net (code "33") (name "/DATA_SICK_4") (class "Default")
      (node (ref "JP6") (pin "3") (pinfunction "3_3") (pintype "passive"))
      (node (ref "R9") (pin "2") (pinfunction "2_2") (pintype "passive"))
    )
    (net (code "34") (name "/DETECT_10V") (class "Default")
      (node (ref "IC1") (pin "30") (pinfunction "OSC1/CLKI/CN30/RA2_30") (pintype "bidirectional"))
      (node (ref "R31") (pin "1") (pinfunction "1_1") (pintype "passive"))
    )
    (net (code "35") (name "/DETECT_V_MOT") (class "Default")
      (node (ref "IC1") (pin "22") (pinfunction "PGEC1/AN3/C2IN+/RP1/CN5/RB1_22") (pintype "bidirectional"))
      (node (ref "R32") (pin "1") (pinfunction "1_1") (pintype "passive"))
    )
    (net (code "36") (name "/DIREC1") (class "Default")
      (node (ref "IC1") (pin "15") (pinfunction "PWM1L1/RP15/CN11/PMCS1/RB15_15") (pintype "bidirectional"))
      (node (ref "IC4") (pin "3") (pinfunction "DIRECTION_3") (pintype "input"))
      (node (ref "PAD10") (pin "P$1") (pinfunction "P$1_P$1") (pintype "bidirectional"))
    )
    (net (code "37") (name "/DIREC2") (class "Default")
      (node (ref "IC1") (pin "11") (pinfunction "PWM1L2/DAC1RN/RP13/CN13/PMRD/RB13_11") (pintype "bidirectional"))
      (node (ref "IC5") (pin "3") (pinfunction "DIRECTION_3") (pintype "input"))
      (node (ref "PAD7") (pin "P$1") (pinfunction "P$1_P$1") (pintype "bidirectional"))
    )
    (net (code "38") (name "/I2C_SCL1") (class "Default")
      (node (ref "IC1") (pin "44") (pinfunction "SCL1/RP8/CN22/PMD4/RB8_44") (pintype "bidirectional"))
      (node (ref "JP28") (pin "4") (pinfunction "4_4") (pintype "passive"))
      (node (ref "R26") (pin "1") (pinfunction "1_1") (pintype "passive"))
    )
    (net (code "39") (name "/I2C_SDA1") (class "Default")
      (node (ref "IC1") (pin "1") (pinfunction "SDA1/RP9/CN21/PMD3/RB9_1") (pintype "bidirectional"))
      (node (ref "JP28") (pin "3") (pinfunction "3_3") (pintype "passive"))
      (node (ref "R25") (pin "1") (pinfunction "1_1") (pintype "passive"))
    )
    (net (code "40") (name "/INHIBIT_10V") (class "Default")
      (node (ref "PI1") (pin "1") (pinfunction "1_1") (pintype "bidirectional"))
      (node (ref "U$2") (pin "3") (pinfunction "/INHIBIT_3") (pintype "bidirectional"))
    )
    (net (code "41") (name "/INHIBIT_MOT") (class "Default")
      (node (ref "PI1") (pin "3") (pinfunction "3_3") (pintype "bidirectional"))
      (node (ref "U$5") (pin "3") (pinfunction "/INHIBIT_3") (pintype "bidirectional"))
    )
    (net (code "42") (name "/MOTEUR1A") (class "Default")
      (node (ref "C12") (pin "1") (pinfunction "1_1") (pintype "passive"))
      (node (ref "IC4") (pin "2") (pinfunction "OUTPUT1_2") (pintype "output"))
      (node (ref "JP18") (pin "1") (pinfunction "1_1") (pintype "passive"))
    )
    (net (code "43") (name "/MOTEUR1B") (class "Default")
      (node (ref "C13") (pin "2") (pinfunction "2_2") (pintype "passive"))
      (node (ref "IC4") (pin "10") (pinfunction "OUTPUT2_10") (pintype "output"))
      (node (ref "JP18") (pin "2") (pinfunction "2_2") (pintype "passive"))
    )
    (net (code "44") (name "/MOTEUR2A") (class "Default")
      (node (ref "C16") (pin "1") (pinfunction "1_1") (pintype "passive"))
      (node (ref "IC5") (pin "2") (pinfunction "OUTPUT1_2") (pintype "output"))
      (node (ref "JP19") (pin "1") (pinfunction "1_1") (pintype "passive"))
    )
    (net (code "45") (name "/MOTEUR2B") (class "Default")
      (node (ref "C17") (pin "2") (pinfunction "2_2") (pintype "passive"))
      (node (ref "IC5") (pin "10") (pinfunction "OUTPUT2_10") (pintype "output"))
      (node (ref "JP19") (pin "2") (pinfunction "2_2") (pintype "passive"))
    )
    (net (code "46") (name "/M_CLR") (class "Default")
      (node (ref "IC1") (pin "18") (pinfunction "MCLR_18") (pintype "input"))
      (node (ref "PS1") (pin "4") (pinfunction "2_4") (pintype "bidirectional"))
      (node (ref "R24") (pin "2") (pinfunction "2_2") (pintype "passive"))
      (node (ref "SV1") (pin "5") (pinfunction "5_5") (pintype "passive"))
      (node (ref "T1") (pin "3") (pinfunction "D_3") (pintype "bidirectional"))
    )
    (net (code "47") (name "/PGC") (class "Default")
      (node (ref "IC1") (pin "42") (pinfunction "PGEC3/ASCL1/RP6/CN24/PMD6/RB6_42") (pintype "bidirectional"))
      (node (ref "SV1") (pin "1") (pinfunction "1_1") (pintype "passive"))
    )
    (net (code "48") (name "/PGD") (class "Default")
      (node (ref "IC1") (pin "41") (pinfunction "PGED3/ASDA1/RP5/CN27/PMD7/RB5_41") (pintype "bidirectional"))
      (node (ref "SV1") (pin "2") (pinfunction "2_2") (pintype "passive"))
    )
    (net (code "49") (name "/PWM1") (class "Default")
      (node (ref "IC1") (pin "14") (pinfunction "PWM1H1/RTCC/RP14/CN12/PMWR/RB14_14") (pintype "bidirectional"))
      (node (ref "IC4") (pin "5") (pinfunction "PWM_5") (pintype "input"))
      (node (ref "PAD9") (pin "P$1") (pinfunction "P$1_P$1") (pintype "bidirectional"))
    )
    (net (code "50") (name "/PWM2") (class "Default")
      (node (ref "IC1") (pin "10") (pinfunction "PWM1H2/DAC1RP/RP12/CN14/PMD0/RB12_10") (pintype "bidirectional"))
      (node (ref "IC5") (pin "5") (pinfunction "PWM_5") (pintype "input"))
      (node (ref "PAD6") (pin "P$1") (pinfunction "P$1_P$1") (pintype "bidirectional"))
    )
    (net (code "51") (name "/RST_PIC_FROM_RPI") (class "Default")
      (node (ref "R33") (pin "2") (pinfunction "2_2") (pintype "passive"))
      (node (ref "T1") (pin "1") (pinfunction "G_1") (pintype "bidirectional"))
      (node (ref "X1") (pin "11") (pinfunction "GPIO17_11") (pintype "bidirectional"))
    )
    (net (code "52") (name "/RX_PIC") (class "Default")
      (node (ref "IC1") (pin "27") (pinfunction "AN8/CVREF/RP18/PMA2/CN10/RC2_27") (pintype "bidirectional"))
      (node (ref "U$9") (pin "C") (pinfunction "C_C") (pintype "bidirectional"))
    )
    (net (code "53") (name "/SENSE1") (class "Default")
      (node (ref "IC4") (pin "8") (pinfunction "SENSE_8") (pintype "output"))
      (node (ref "PAD12") (pin "P$1") (pinfunction "P$1_P$1") (pintype "bidirectional"))
      (node (ref "R15") (pin "2") (pinfunction "2_2") (pintype "passive"))
      (node (ref "R17") (pin "2") (pinfunction "2_2") (pintype "passive"))
    )
    (net (code "54") (name "/SENSE2") (class "Default")
      (node (ref "IC5") (pin "8") (pinfunction "SENSE_8") (pintype "output"))
      (node (ref "PAD13") (pin "P$1") (pinfunction "P$1_P$1") (pintype "bidirectional"))
      (node (ref "R16") (pin "2") (pinfunction "2_2") (pintype "passive"))
      (node (ref "R18") (pin "2") (pinfunction "2_2") (pintype "passive"))
    )
    (net (code "55") (name "/SENSE_V_BAT") (class "Default")
      (node (ref "C27") (pin "1") (pinfunction "1_1") (pintype "passive"))
      (node (ref "IC1") (pin "19") (pinfunction "AN0/VREF+/CN2/RA0_19") (pintype "bidirectional"))
      (node (ref "R22") (pin "2") (pinfunction "2_2") (pintype "passive"))
      (node (ref "R23") (pin "1") (pinfunction "1_1") (pintype "passive"))
    )
    (net (code "56") (name "/THERMAL") (class "Default")
      (node (ref "IC1") (pin "12") (pinfunction "TMS/PMA10/RA10_12") (pintype "bidirectional"))
      (node (ref "IC4") (pin "9") (pinfunction "THERMAL_9") (pintype "output"))
      (node (ref "IC5") (pin "9") (pinfunction "THERMAL_9") (pintype "output"))
      (node (ref "PAD2") (pin "P$1") (pinfunction "P$1_P$1") (pintype "bidirectional"))
      (node (ref "R13") (pin "1") (pinfunction "1_1") (pintype "passive"))
    )
    (net (code "57") (name "/TX_FTDI") (class "Default")
      (node (ref "IC3") (pin "1") (pinfunction "TXD_1") (pintype "output"))
      (node (ref "U$9") (pin "3") (pinfunction "3_3") (pintype "bidirectional"))
    )
    (net (code "58") (name "/TX_PIC") (class "Default")
      (node (ref "IC1") (pin "33") (pinfunction "SOSCI/RP4/CN1/RB4_33") (pintype "bidirectional"))
      (node (ref "IC3") (pin "4") (pinfunction "RXD_4") (pintype "input"))
      (node (ref "PAD17") (pin "P$1") (pinfunction "P$1_P$1") (pintype "bidirectional"))
      (node (ref "X1") (pin "10") (pinfunction "RXD_10") (pintype "bidirectional"))
      (node (ref "XB1") (pin "3") (pinfunction "DIN/~{CONFIG}_3") (pintype "input"))
    )
    (net (code "59") (name "/TX_RPI") (class "Default")
      (node (ref "U$9") (pin "2") (pinfunction "2_2") (pintype "bidirectional"))
      (node (ref "X1") (pin "8") (pinfunction "TXD_8") (pintype "bidirectional"))
    )
    (net (code "60") (name "/TX_XBEE") (class "Default")
      (node (ref "U$9") (pin "1") (pinfunction "1_1") (pintype "bidirectional"))
      (node (ref "XB1") (pin "2") (pinfunction "DOUT_2") (pintype "output"))
    )
    (net (code "61") (name "/USB_D+") (class "Default")
      (node (ref "IC3") (pin "8") (pinfunction "USBDP_8") (pintype "input"))
      (node (ref "JP20") (pin "D+") (pinfunction "D+_D+") (pintype "bidirectional"))
      (node (ref "P1") (pin "3") (pinfunction "D+_3") (pintype "bidirectional"))
    )
    (net (code "62") (name "/USB_D-") (class "Default")
      (node (ref "IC3") (pin "9") (pinfunction "USBDM_9") (pintype "input"))
      (node (ref "JP20") (pin "D-") (pinfunction "D-_D-") (pintype "bidirectional"))
      (node (ref "P1") (pin "2") (pinfunction "D-_2") (pintype "bidirectional"))
    )
    (net (code "63") (name "/VCAP{slash}VDDCORE") (class "Default")
      (node (ref "C24") (pin "1") (pinfunction "1_1") (pintype "passive"))
      (node (ref "IC1") (pin "7") (pinfunction "VCAP/VDDCORE_7") (pintype "power_in"))
    )
    (net (code "64") (name "/VIN") (class "Default")
      (node (ref "C10") (pin "P") (pinfunction "P_P") (pintype "passive"))
      (node (ref "C20") (pin "1") (pinfunction "1_1") (pintype "passive"))
      (node (ref "C28") (pin "1") (pinfunction "1_1") (pintype "passive"))
      (node (ref "C29") (pin "1") (pinfunction "1_1") (pintype "passive"))
      (node (ref "C4") (pin "1") (pinfunction "1_1") (pintype "passive"))
      (node (ref "D6") (pin "A") (pinfunction "A_A") (pintype "passive"))
      (node (ref "F1") (pin "1A") (pinfunction "1A_1A") (pintype "passive"))
      (node (ref "F1") (pin "1B") (pinfunction "1B_1B") (pintype "passive"))
      (node (ref "R4") (pin "2") (pinfunction "2_2") (pintype "passive"))
      (node (ref "U$2") (pin "2") (pinfunction "VIN_2") (pintype "bidirectional"))
      (node (ref "U$5") (pin "2") (pinfunction "VIN_2") (pintype "bidirectional"))
    )
    (net (code "65") (name "/V_BAT") (class "Default")
      (node (ref "D1") (pin "A") (pinfunction "A_A") (pintype "passive"))
      (node (ref "D2") (pin "A") (pinfunction "A_A") (pintype "passive"))
      (node (ref "JP1") (pin "1") (pinfunction "1_1") (pintype "passive"))
      (node (ref "R22") (pin "1") (pinfunction "1_1") (pintype "passive"))
    )
    (net (code "66") (name "/V_MOTEUR") (class "Default")
      (node (ref "C14") (pin "1") (pinfunction "1_1") (pintype "passive"))
      (node (ref "C15") (pin "1") (pinfunction "1_1") (pintype "passive"))
      (node (ref "IC4") (pin "6") (pinfunction "VS_6") (pintype "power_in"))
      (node (ref "IC5") (pin "6") (pinfunction "VS_6") (pintype "power_in"))
      (node (ref "JP26") (pin "1") (pinfunction "1_1") (pintype "passive"))
      (node (ref "PI2") (pin "1") (pinfunction "1_1") (pintype "bidirectional"))
      (node (ref "R28") (pin "1") (pinfunction "1_1") (pintype "passive"))
    )
    (net (code "67") (name "/V_MOT_OUT") (class "Default")
      (node (ref "C21") (pin "P") (pinfunction "P_P") (pintype "passive"))
      (node (ref "C22") (pin "1") (pinfunction "1_1") (pintype "passive"))
      (node (ref "JP26") (pin "2") (pinfunction "2_2") (pintype "passive"))
      (node (ref "PAD4") (pin "P$1") (pinfunction "P$1_P$1") (pintype "bidirectional"))
      (node (ref "PI2") (pin "2") (pinfunction "2_2") (pintype "bidirectional"))
      (node (ref "U$5") (pin "5") (pinfunction "VSENSE_5") (pintype "bidirectional"))
      (node (ref "U$5") (pin "6") (pinfunction "VOUT_6") (pintype "bidirectional"))
    )
    (net (code "68") (name "GND") (class "Default")
      (node (ref "C1") (pin "2") (pinfunction "2_2") (pintype "passive"))
      (node (ref "C10") (pin "N") (pinfunction "N_N") (pintype "passive"))
      (node (ref "C11") (pin "2") (pinfunction "2_2") (pintype "passive"))
      (node (ref "C14") (pin "2") (pinfunction "2_2") (pintype "passive"))
      (node (ref "C15") (pin "2") (pinfunction "2_2") (pintype "passive"))
      (node (ref "C18") (pin "2") (pinfunction "2_2") (pintype "passive"))
      (node (ref "C19") (pin "2") (pinfunction "2_2") (pintype "passive"))
      (node (ref "C2") (pin "2") (pinfunction "2_2") (pintype "passive"))
      (node (ref "C20") (pin "2") (pinfunction "2_2") (pintype "passive"))
      (node (ref "C21") (pin "N") (pinfunction "N_N") (pintype "passive"))
      (node (ref "C22") (pin "2") (pinfunction "2_2") (pintype "passive"))
      (node (ref "C23") (pin "2") (pinfunction "2_2") (pintype "passive"))
      (node (ref "C24") (pin "2") (pinfunction "2_2") (pintype "passive"))
      (node (ref "C25") (pin "2") (pinfunction "2_2") (pintype "passive"))
      (node (ref "C26") (pin "2") (pinfunction "2_2") (pintype "passive"))
      (node (ref "C27") (pin "2") (pinfunction "2_2") (pintype "passive"))
      (node (ref "C28") (pin "2") (pinfunction "2_2") (pintype "passive"))
      (node (ref "C29") (pin "2") (pinfunction "2_2") (pintype "passive"))
      (node (ref "C3") (pin "2") (pinfunction "2_2") (pintype "passive"))
      (node (ref "C30") (pin "2") (pinfunction "2_2") (pintype "passive"))
      (node (ref "C31") (pin "2") (pinfunction "2_2") (pintype "passive"))
      (node (ref "C32") (pin "2") (pinfunction "2_2") (pintype "passive"))
      (node (ref "C33") (pin "2") (pinfunction "2_2") (pintype "passive"))
      (node (ref "C34") (pin "2") (pinfunction "2_2") (pintype "passive"))
      (node (ref "C35") (pin "2") (pinfunction "2_2") (pintype "passive"))
      (node (ref "C36") (pin "2") (pinfunction "2_2") (pintype "passive"))
      (node (ref "C37") (pin "2") (pinfunction "2_2") (pintype "passive"))
      (node (ref "C38") (pin "2") (pinfunction "2_2") (pintype "passive"))
      (node (ref "C39") (pin "2") (pinfunction "2_2") (pintype "passive"))
      (node (ref "C4") (pin "2") (pinfunction "2_2") (pintype "passive"))
      (node (ref "C5") (pin "2") (pinfunction "2_2") (pintype "passive"))
      (node (ref "C6") (pin "N") (pinfunction "N_N") (pintype "passive"))
      (node (ref "C7") (pin "N") (pinfunction "N_N") (pintype "passive"))
      (node (ref "C8") (pin "2") (pinfunction "2_2") (pintype "passive"))
      (node (ref "C9") (pin "2") (pinfunction "2_2") (pintype "passive"))
      (node (ref "IC1") (pin "16") (pinfunction "AVSS_16") (pintype "power_in"))
      (node (ref "IC1") (pin "29") (pinfunction "VSS1_29") (pintype "power_in"))
      (node (ref "IC1") (pin "39") (pinfunction "VSS2_39") (pintype "power_in"))
      (node (ref "IC1") (pin "6") (pinfunction "VSS_6") (pintype "power_in"))
      (node (ref "IC2") (pin "GND") (pinfunction "GND_GND") (pintype "input"))
      (node (ref "IC3") (pin "13") (pinfunction "GND_13") (pintype "power_in"))
      (node (ref "IC3") (pin "5") (pinfunction "GND_5") (pintype "power_in"))
      (node (ref "IC4") (pin "7") (pinfunction "GND_7") (pintype "power_in"))
      (node (ref "IC5") (pin "7") (pinfunction "GND_7") (pintype "power_in"))
      (node (ref "JP1") (pin "2") (pinfunction "2_2") (pintype "passive"))
      (node (ref "JP10") (pin "1") (pinfunction "1_1") (pintype "passive"))
      (node (ref "JP11") (pin "1") (pinfunction "1_1") (pintype "passive"))
      (node (ref "JP12") (pin "1") (pinfunction "1_1") (pintype "passive"))
      (node (ref "JP13") (pin "1") (pinfunction "1_1") (pintype "passive"))
      (node (ref "JP14") (pin "1") (pinfunction "1_1") (pintype "passive"))
      (node (ref "JP15") (pin "1") (pinfunction "1_1") (pintype "passive"))
      (node (ref "JP16") (pin "4") (pinfunction "4_4") (pintype "passive"))
      (node (ref "JP17") (pin "4") (pinfunction "4_4") (pintype "passive"))
      (node (ref "JP2") (pin "1") (pinfunction "1_1") (pintype "passive"))
      (node (ref "JP20") (pin "GND") (pinfunction "GND_GND") (pintype "bidirectional"))
      (node (ref "JP21") (pin "1") (pinfunction "1_1") (pintype "passive"))
      (node (ref "JP22") (pin "1") (pinfunction "1_1") (pintype "passive"))
      (node (ref "JP23") (pin "1") (pinfunction "1_1") (pintype "passive"))
      (node (ref "JP24") (pin "1") (pinfunction "1_1") (pintype "passive"))
      (node (ref "JP25") (pin "2") (pinfunction "2_2") (pintype "passive"))
      (node (ref "JP28") (pin "1") (pinfunction "1_1") (pintype "passive"))
      (node (ref "JP29") (pin "B1") (pinfunction "GND_B1") (pintype "bidirectional"))
      (node (ref "JP29") (pin "B2") (pinfunction "GND_B2") (pintype "bidirectional"))
      (node (ref "JP29") (pin "GND") (pinfunction "GND_GND") (pintype "bidirectional"))
      (node (ref "JP3") (pin "1") (pinfunction "1_1") (pintype "passive"))
      (node (ref "JP4") (pin "1") (pinfunction "1_1") (pintype "passive"))
      (node (ref "JP5") (pin "1") (pinfunction "1_1") (pintype "passive"))
      (node (ref "JP6") (pin "1") (pinfunction "1_1") (pintype "passive"))
      (node (ref "JP7") (pin "1") (pinfunction "1_1") (pintype "passive"))
      (node (ref "JP8") (pin "1") (pinfunction "1_1") (pintype "passive"))
      (node (ref "JP9") (pin "1") (pinfunction "1_1") (pintype "passive"))
      (node (ref "LED1") (pin "K") (pinfunction "K_K") (pintype "passive"))
      (node (ref "LED2") (pin "K") (pinfunction "K_K") (pintype "passive"))
      (node (ref "LED3") (pin "K") (pinfunction "K_K") (pintype "passive"))
      (node (ref "P1") (pin "5") (pinfunction "GND_5") (pintype "bidirectional"))
      (node (ref "P1") (pin "SH@1") (pinfunction "PT1_SH@1") (pintype "bidirectional"))
      (node (ref "P1") (pin "SH@2") (pinfunction "PT2_SH@2") (pintype "bidirectional"))
      (node (ref "P1") (pin "SH@3") (pinfunction "PT3_SH@3") (pintype "bidirectional"))
      (node (ref "P1") (pin "SH@4") (pinfunction "PT4_SH@4") (pintype "bidirectional"))
      (node (ref "PS1") (pin "1") (pinfunction "1_1") (pintype "bidirectional"))
      (node (ref "R1") (pin "2") (pinfunction "2_2") (pintype "passive"))
      (node (ref "R10") (pin "1") (pinfunction "1_1") (pintype "passive"))
      (node (ref "R12") (pin "1") (pinfunction "1_1") (pintype "passive"))
      (node (ref "R14") (pin "2") (pinfunction "2_2") (pintype "passive"))
      (node (ref "R15") (pin "1") (pinfunction "1_1") (pintype "passive"))
      (node (ref "R16") (pin "1") (pinfunction "1_1") (pintype "passive"))
      (node (ref "R19") (pin "2") (pinfunction "2_2") (pintype "passive"))
      (node (ref "R2") (pin "2") (pinfunction "2_2") (pintype "passive"))
      (node (ref "R23") (pin "2") (pinfunction "2_2") (pintype "passive"))
      (node (ref "R29") (pin "2") (pinfunction "2_2") (pintype "passive"))
      (node (ref "R30") (pin "2") (pinfunction "2_2") (pintype "passive"))
      (node (ref "R33") (pin "1") (pinfunction "1_1") (pintype "passive"))
      (node (ref "R34") (pin "2") (pinfunction "2_2") (pintype "passive"))
      (node (ref "R35") (pin "2") (pinfunction "2_2") (pintype "passive"))
      (node (ref "R6") (pin "1") (pinfunction "1_1") (pintype "passive"))
      (node (ref "R8") (pin "1") (pinfunction "1_1") (pintype "passive"))
      (node (ref "SV1") (pin "3") (pinfunction "3_3") (pintype "passive"))
      (node (ref "T1") (pin "2") (pinfunction "S_2") (pintype "bidirectional"))
      (node (ref "U$1") (pin "1") (pinfunction "GND_1") (pintype "bidirectional"))
      (node (ref "U$1") (pin "7") (pinfunction "GND_7") (pintype "bidirectional"))
      (node (ref "U$2") (pin "1") (pinfunction "GND_1") (pintype "bidirectional"))
      (node (ref "U$2") (pin "7") (pinfunction "GND_7") (pintype "bidirectional"))
      (node (ref "U$5") (pin "1") (pinfunction "GND_1") (pintype "bidirectional"))
      (node (ref "U$5") (pin "7") (pinfunction "GND_7") (pintype "bidirectional"))
      (node (ref "X1") (pin "14") (pinfunction "GND_C_14") (pintype "power_in"))
      (node (ref "X1") (pin "20") (pinfunction "GND_E_20") (pintype "power_in"))
      (node (ref "X1") (pin "25") (pinfunction "GND_F_25") (pintype "power_in"))
      (node (ref "X1") (pin "41") (pinfunction "GND_A_41") (pintype "power_in"))
      (node (ref "X1") (pin "42") (pinfunction "GND_A_42") (pintype "power_in"))
      (node (ref "X1") (pin "43") (pinfunction "GND_A_43") (pintype "power_in"))
      (node (ref "X1") (pin "44") (pinfunction "GND_A_44") (pintype "power_in"))
      (node (ref "X1") (pin "45") (pinfunction "GND_A_45") (pintype "power_in"))
      (node (ref "X1") (pin "46") (pinfunction "GND_A_46") (pintype "power_in"))
      (node (ref "X1") (pin "6") (pinfunction "GND_A_6") (pintype "power_in"))
      (node (ref "X1") (pin "9") (pinfunction "GND_B_9") (pintype "power_in"))
      (node (ref "XB1") (pin "10") (pinfunction "GND_10") (pintype "power_in"))
    )
    (net (code "69") (name "Net-(D1-PadK)") (class "Default")
      (node (ref "D1") (pin "K") (pinfunction "K_K") (pintype "passive"))
      (node (ref "D2") (pin "K") (pinfunction "K_K") (pintype "passive"))
      (node (ref "F1") (pin "2A") (pinfunction "2A_2A") (pintype "passive"))
      (node (ref "F1") (pin "2B") (pinfunction "2B_2B") (pintype "passive"))
    )
    (net (code "70") (name "Net-(IC4-BOOTSTRAP1)") (class "Default")
      (node (ref "C12") (pin "2") (pinfunction "2_2") (pintype "passive"))
      (node (ref "IC4") (pin "1") (pinfunction "BOOTSTRAP1_1") (pintype "input"))
    )
    (net (code "71") (name "Net-(IC4-BOOTSTRAP2)") (class "Default")
      (node (ref "C13") (pin "1") (pinfunction "1_1") (pintype "passive"))
      (node (ref "IC4") (pin "11") (pinfunction "BOOTSTRAP2_11") (pintype "input"))
    )
    (net (code "72") (name "Net-(IC5-BOOTSTRAP1)") (class "Default")
      (node (ref "C16") (pin "2") (pinfunction "2_2") (pintype "passive"))
      (node (ref "IC5") (pin "1") (pinfunction "BOOTSTRAP1_1") (pintype "input"))
    )
    (net (code "73") (name "Net-(IC5-BOOTSTRAP2)") (class "Default")
      (node (ref "C17") (pin "1") (pinfunction "1_1") (pintype "passive"))
      (node (ref "IC5") (pin "11") (pinfunction "BOOTSTRAP2_11") (pintype "input"))
    )
    (net (code "74") (name "Net-(JP25-Pad1)") (class "Default")
      (node (ref "JP25") (pin "1") (pinfunction "1_1") (pintype "passive"))
      (node (ref "PI1") (pin "2") (pinfunction "2_2") (pintype "bidirectional"))
    )
    (net (code "75") (name "Net-(JP28-Pad2)") (class "Default")
      (node (ref "JP28") (pin "2") (pinfunction "2_2") (pintype "passive"))
      (node (ref "PI4") (pin "2") (pinfunction "2_2") (pintype "bidirectional"))
      (node (ref "R25") (pin "2") (pinfunction "2_2") (pintype "passive"))
      (node (ref "R26") (pin "2") (pinfunction "2_2") (pintype "passive"))
    )
    (net (code "76") (name "Net-(LED1-PadA)") (class "Default")
      (node (ref "LED1") (pin "A") (pinfunction "A_A") (pintype "passive"))
      (node (ref "R4") (pin "1") (pinfunction "1_1") (pintype "passive"))
    )
    (net (code "77") (name "Net-(LED2-PadA)") (class "Default")
      (node (ref "LED2") (pin "A") (pinfunction "A_A") (pintype "passive"))
      (node (ref "R3") (pin "1") (pinfunction "1_1") (pintype "passive"))
    )
    (net (code "78") (name "Net-(LED3-PadA)") (class "Default")
      (node (ref "LED3") (pin "A") (pinfunction "A_A") (pintype "passive"))
      (node (ref "R37") (pin "1") (pinfunction "1_1") (pintype "passive"))
    )
    (net (code "79") (name "Net-(R27-Pad2)") (class "Default")
      (node (ref "R27") (pin "2") (pinfunction "2_2") (pintype "passive"))
      (node (ref "R29") (pin "1") (pinfunction "1_1") (pintype "passive"))
      (node (ref "R31") (pin "2") (pinfunction "2_2") (pintype "passive"))
    )
    (net (code "80") (name "Net-(R28-Pad2)") (class "Default")
      (node (ref "R28") (pin "2") (pinfunction "2_2") (pintype "passive"))
      (node (ref "R30") (pin "1") (pinfunction "1_1") (pintype "passive"))
      (node (ref "R32") (pin "2") (pinfunction "2_2") (pintype "passive"))
    )
    (net (code "81") (name "Net-(R34-Pad1)") (class "Default")
      (node (ref "R34") (pin "1") (pinfunction "1_1") (pintype "passive"))
      (node (ref "R36") (pin "2") (pinfunction "2_2") (pintype "passive"))
    )
    (net (code "82") (name "Net-(U$1-RSET)") (class "Default")
      (node (ref "R2") (pin "1") (pinfunction "1_1") (pintype "passive"))
      (node (ref "U$1") (pin "4") (pinfunction "RSET_4") (pintype "bidirectional"))
    )
    (net (code "83") (name "Net-(U$1-VIN)") (class "Default")
      (node (ref "C5") (pin "1") (pinfunction "1_1") (pintype "passive"))
      (node (ref "D6") (pin "K") (pinfunction "K_K") (pintype "passive"))
      (node (ref "U$1") (pin "2") (pinfunction "VIN_2") (pintype "bidirectional"))
    )
    (net (code "84") (name "Net-(U$2-RSET)") (class "Default")
      (node (ref "R1") (pin "1") (pinfunction "1_1") (pintype "passive"))
      (node (ref "U$2") (pin "4") (pinfunction "RSET_4") (pintype "bidirectional"))
    )
    (net (code "85") (name "Net-(U$5-RSET)") (class "Default")
      (node (ref "R14") (pin "1") (pinfunction "1_1") (pintype "passive"))
      (node (ref "R19") (pin "1") (pinfunction "1_1") (pintype "passive"))
      (node (ref "R35") (pin "1") (pinfunction "1_1") (pintype "passive"))
      (node (ref "R36") (pin "1") (pinfunction "1_1") (pintype "passive"))
      (node (ref "U$5") (pin "4") (pinfunction "RSET_4") (pintype "bidirectional"))
    )
    (net (code "86") (name "Net-(U$12-P$1)") (class "Default")
      (node (ref "PI5") (pin "1") (pinfunction "1_1") (pintype "bidirectional"))
      (node (ref "U$12") (pin "1") (pinfunction "P$1_1") (pintype "bidirectional"))
    )
    (net (code "87") (name "Net-(U$12-P$2)") (class "Default")
      (node (ref "C25") (pin "1") (pinfunction "1_1") (pintype "passive"))
      (node (ref "U$12") (pin "2") (pinfunction "P$2_2") (pintype "bidirectional"))
      (node (ref "X1") (pin "2") (pinfunction "5V0A_2") (pintype "power_in"))
      (node (ref "X1") (pin "4") (pinfunction "5V0B_4") (pintype "power_in"))
    )
    (net (code "88") (name "Net-(X1-GPIO04)") (class "Default")
      (node (ref "R37") (pin "2") (pinfunction "2_2") (pintype "passive"))
      (node (ref "X1") (pin "7") (pinfunction "GPIO04_7") (pintype "bidirectional"))
    )
    (net (code "89") (name "unconnected-(IC3-CBUS0-Pad15)") (class "Default")
      (node (ref "IC3") (pin "15") (pinfunction "CBUS0_15") (pintype "bidirectional"))
    )
    (net (code "90") (name "unconnected-(IC3-CBUS1-Pad14)") (class "Default")
      (node (ref "IC3") (pin "14") (pinfunction "CBUS1_14") (pintype "bidirectional"))
    )
    (net (code "91") (name "unconnected-(IC3-CBUS2-Pad7)") (class "Default")
      (node (ref "IC3") (pin "7") (pinfunction "CBUS2_7") (pintype "bidirectional"))
    )
    (net (code "92") (name "unconnected-(IC3-CBUS3-Pad16)") (class "Default")
      (node (ref "IC3") (pin "16") (pinfunction "CBUS3_16") (pintype "bidirectional"))
    )
    (net (code "93") (name "unconnected-(IC3-~{CTS}-Pad6)") (class "Default")
      (node (ref "IC3") (pin "6") (pinfunction "~{CTS}_6") (pintype "input"))
    )
    (net (code "94") (name "unconnected-(IC3-~{RTS}-Pad2)") (class "Default")
      (node (ref "IC3") (pin "2") (pinfunction "~{RTS}_2") (pintype "output"))
    )
    (net (code "95") (name "unconnected-(JP29-PadD+)") (class "Default")
      (node (ref "JP29") (pin "D+") (pinfunction "D+_D+") (pintype "bidirectional"))
    )
    (net (code "96") (name "unconnected-(JP29-PadD-)") (class "Default")
      (node (ref "JP29") (pin "D-") (pinfunction "D-_D-") (pintype "bidirectional"))
    )
    (net (code "97") (name "unconnected-(P1-ID-Pad4)") (class "Default")
      (node (ref "P1") (pin "4") (pinfunction "ID_4") (pintype "bidirectional"))
    )
    (net (code "98") (name "unconnected-(U$1-{slash}INHIBIT-Pad3)") (class "Default")
      (node (ref "U$1") (pin "3") (pinfunction "/INHIBIT_3") (pintype "bidirectional"))
    )
    (net (code "99") (name "unconnected-(X1-GPIO18-Pad12)") (class "Default")
      (node (ref "X1") (pin "12") (pinfunction "GPIO18_12") (pintype "bidirectional"))
    )
    (net (code "100") (name "unconnected-(X1-GPIO22-Pad15)") (class "Default")
      (node (ref "X1") (pin "15") (pinfunction "GPIO22_15") (pintype "bidirectional"))
    )
    (net (code "101") (name "unconnected-(X1-GPIO23-Pad16)") (class "Default")
      (node (ref "X1") (pin "16") (pinfunction "GPIO23_16") (pintype "bidirectional"))
    )
    (net (code "102") (name "unconnected-(X1-GPIO24-Pad18)") (class "Default")
      (node (ref "X1") (pin "18") (pinfunction "GPIO24_18") (pintype "bidirectional"))
    )
    (net (code "103") (name "unconnected-(X1-GPIO25-Pad22)") (class "Default")
      (node (ref "X1") (pin "22") (pinfunction "GPIO25_22") (pintype "bidirectional"))
    )
    (net (code "104") (name "unconnected-(X1-GPIO27-Pad13)") (class "Default")
      (node (ref "X1") (pin "13") (pinfunction "GPIO27_13") (pintype "bidirectional"))
    )
    (net (code "105") (name "unconnected-(X1-SCL-Pad5)") (class "Default")
      (node (ref "X1") (pin "5") (pinfunction "SCL_5") (pintype "bidirectional"))
    )
    (net (code "106") (name "unconnected-(X1-SDA-Pad3)") (class "Default")
      (node (ref "X1") (pin "3") (pinfunction "SDA_3") (pintype "bidirectional"))
    )
    (net (code "107") (name "unconnected-(X1-SPI_CE0-Pad24)") (class "Default")
      (node (ref "X1") (pin "24") (pinfunction "SPI_CE0_24") (pintype "bidirectional"))
    )
    (net (code "108") (name "unconnected-(X1-SPI_CE1-Pad26)") (class "Default")
      (node (ref "X1") (pin "26") (pinfunction "SPI_CE1_26") (pintype "bidirectional"))
    )
    (net (code "109") (name "unconnected-(X1-SPI_MISO-Pad21)") (class "Default")
      (node (ref "X1") (pin "21") (pinfunction "SPI_MISO_21") (pintype "bidirectional"))
    )
    (net (code "110") (name "unconnected-(X1-SPI_MOSI-Pad19)") (class "Default")
      (node (ref "X1") (pin "19") (pinfunction "SPI_MOSI_19") (pintype "bidirectional"))
    )
    (net (code "111") (name "unconnected-(X1-SPI_SCLK-Pad23)") (class "Default")
      (node (ref "X1") (pin "23") (pinfunction "SPI_SCLK_23") (pintype "bidirectional"))
    )
    (net (code "112") (name "unconnected-(XB1-AD0{slash}DIO0-Pad20)") (class "Default")
      (node (ref "XB1") (pin "20") (pinfunction "AD0/DIO0_20") (pintype "bidirectional"))
    )
    (net (code "113") (name "unconnected-(XB1-AD1{slash}DIO1-Pad19)") (class "Default")
      (node (ref "XB1") (pin "19") (pinfunction "AD1/DIO1_19") (pintype "bidirectional"))
    )
    (net (code "114") (name "unconnected-(XB1-AD2{slash}DIO2-Pad18)") (class "Default")
      (node (ref "XB1") (pin "18") (pinfunction "AD2/DIO2_18") (pintype "bidirectional"))
    )
    (net (code "115") (name "unconnected-(XB1-ASSOC{slash}AD5{slash}DIO5-Pad15)") (class "Default")
      (node (ref "XB1") (pin "15") (pinfunction "ASSOC/AD5/DIO5_15") (pintype "bidirectional"))
    )
    (net (code "116") (name "unconnected-(XB1-CD{slash}DOUT_EN{slash}DO8-Pad4)") (class "Default")
      (node (ref "XB1") (pin "4") (pinfunction "CD/DOUT_EN/DO8_4") (pintype "output"))
    )
    (net (code "117") (name "unconnected-(XB1-COORD_SEL{slash}AD3{slash}DIO3-Pad17)") (class "Default")
      (node (ref "XB1") (pin "17") (pinfunction "COORD_SEL/AD3/DIO3_17") (pintype "bidirectional"))
    )
    (net (code "118") (name "unconnected-(XB1-ON{slash}~{SLEEP}-Pad13)") (class "Default")
      (node (ref "XB1") (pin "13") (pinfunction "ON/~{SLEEP}_13") (pintype "output"))
    )
    (net (code "119") (name "unconnected-(XB1-PWM0{slash}RSSI-Pad6)") (class "Default")
      (node (ref "XB1") (pin "6") (pinfunction "PWM0/RSSI_6") (pintype "output"))
    )
    (net (code "120") (name "unconnected-(XB1-RF_TX{slash}AD4{slash}DIO4-Pad11)") (class "Default")
      (node (ref "XB1") (pin "11") (pinfunction "RF_TX/AD4/DIO4_11") (pintype "bidirectional"))
    )
    (net (code "121") (name "unconnected-(XB1-VREF-Pad14)") (class "Default")
      (node (ref "XB1") (pin "14") (pinfunction "VREF_14") (pintype "input"))
    )
    (net (code "122") (name "unconnected-(XB1-~{CTS}{slash}DIO7-Pad12)") (class "Default")
      (node (ref "XB1") (pin "12") (pinfunction "~{CTS}/DIO7_12") (pintype "bidirectional"))
    )
    (net (code "123") (name "unconnected-(XB1-~{DTR}{slash}SLEEP_RQ{slash}DI8-Pad9)") (class "Default")
      (node (ref "XB1") (pin "9") (pinfunction "~{DTR}/SLEEP_RQ/DI8_9") (pintype "bidirectional"))
    )
    (net (code "124") (name "unconnected-(XB1-~{RESET}-Pad5)") (class "Default")
      (node (ref "XB1") (pin "5") (pinfunction "~{RESET}_5") (pintype "input"))
    )
    (net (code "125") (name "unconnected-(XB1-~{RTS}{slash}AD6{slash}DIO6-Pad16)") (class "Default")
      (node (ref "XB1") (pin "16") (pinfunction "~{RTS}/AD6/DIO6_16") (pintype "bidirectional"))
    )
  )
)
